# rp3a-mini-power.net
KiCad netlist of a schematic drawn in Altium Designer
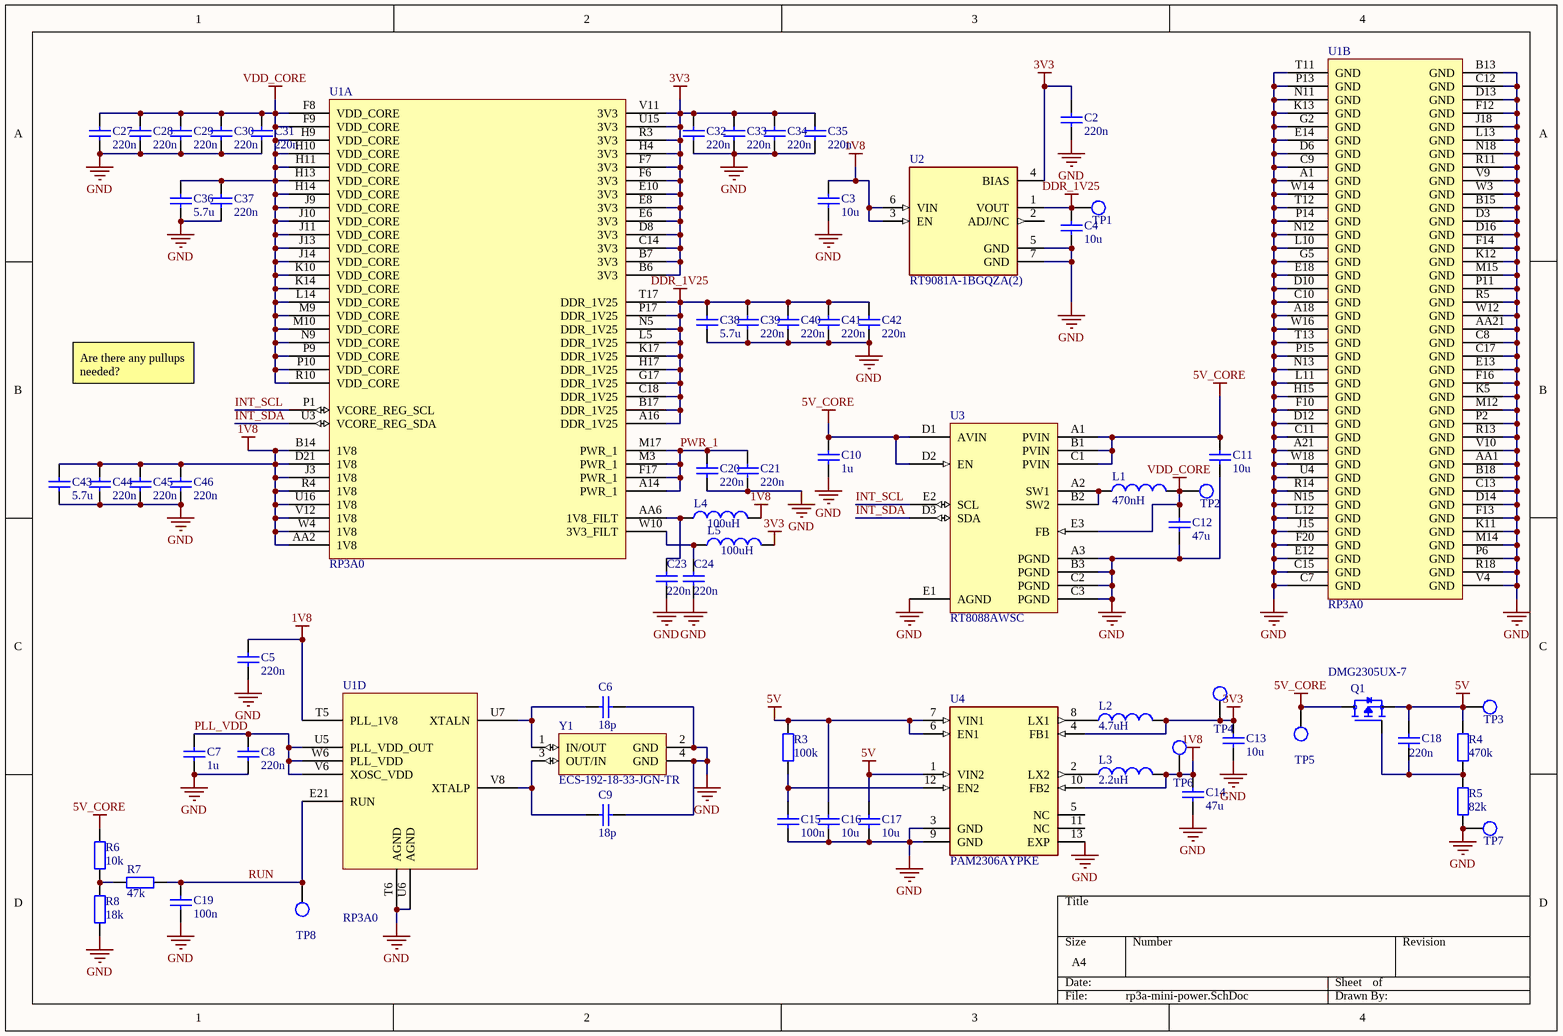
[diagram p0: rp3a-mini-power.SchDoc]

(export (version "E")
  (design (tool "Eeschema 10.0.6"))
  (components
    (comp (ref "C2")
      (value "220n")
      (footprint "0402")
      (description "Capacitor")
      (fields (field (name "Comment") "Cap"))
      (libsource (lib "custom-lib") (part "CAP-NONPOL"))
    )
    (comp (ref "C3")
      (value "10u")
      (footprint "0603")
      (description "Capacitor")
      (fields (field (name "Comment") "Cap"))
      (libsource (lib "custom-lib") (part "CAP-NONPOL"))
    )
    (comp (ref "C4")
      (value "10u")
      (footprint "0603")
      (description "Capacitor")
      (fields (field (name "Comment") "Cap"))
      (libsource (lib "custom-lib") (part "CAP-NONPOL"))
    )
    (comp (ref "C5")
      (value "220n")
      (footprint "0402")
      (description "Capacitor")
      (fields (field (name "Comment") "Cap"))
      (libsource (lib "custom-lib") (part "CAP-NONPOL"))
    )
    (comp (ref "C6")
      (value "18p")
      (footprint "0402")
      (description "Capacitor")
      (fields (field (name "Comment") "Cap"))
      (libsource (lib "custom-lib") (part "CAP-NONPOL"))
    )
    (comp (ref "C7")
      (value "1u")
      (footprint "0402")
      (description "Capacitor")
      (fields (field (name "Comment") "Cap"))
      (libsource (lib "custom-lib") (part "CAP-NONPOL"))
    )
    (comp (ref "C8")
      (value "220n")
      (footprint "0402")
      (description "Capacitor")
      (fields (field (name "Comment") "Cap"))
      (libsource (lib "custom-lib") (part "CAP-NONPOL"))
    )
    (comp (ref "C9")
      (value "18p")
      (footprint "0402")
      (description "Capacitor")
      (fields (field (name "Comment") "Cap"))
      (libsource (lib "custom-lib") (part "CAP-NONPOL"))
    )
    (comp (ref "C10")
      (value "1u")
      (footprint "0402")
      (description "Capacitor")
      (fields (field (name "Comment") "Cap"))
      (libsource (lib "custom-lib") (part "CAP-NONPOL"))
    )
    (comp (ref "C11")
      (value "10u")
      (footprint "0603")
      (description "Capacitor")
      (fields (field (name "Comment") "Cap"))
      (libsource (lib "custom-lib") (part "CAP-NONPOL"))
    )
    (comp (ref "C12")
      (value "47u")
      (footprint "C0805 NP")
      (description "Capacitor")
      (fields (field (name "Comment") "Cap"))
      (libsource (lib "custom-lib") (part "CAP-NONPOL"))
    )
    (comp (ref "C13")
      (value "10u")
      (footprint "0603")
      (description "Capacitor")
      (fields (field (name "Comment") "Cap"))
      (libsource (lib "custom-lib") (part "CAP-NONPOL"))
    )
    (comp (ref "C14")
      (value "47u")
      (footprint "C0805 NP")
      (description "Capacitor")
      (fields (field (name "Comment") "Cap"))
      (libsource (lib "custom-lib") (part "CAP-NONPOL"))
    )
    (comp (ref "C15")
      (value "100n")
      (footprint "0402")
      (description "Capacitor")
      (fields (field (name "Comment") "Cap"))
      (libsource (lib "custom-lib") (part "CAP-NONPOL"))
    )
    (comp (ref "C16")
      (value "10u")
      (footprint "0603")
      (description "Capacitor")
      (fields (field (name "Comment") "Cap"))
      (libsource (lib "custom-lib") (part "CAP-NONPOL"))
    )
    (comp (ref "C17")
      (value "10u")
      (footprint "0603")
      (description "Capacitor")
      (fields (field (name "Comment") "Cap"))
      (libsource (lib "custom-lib") (part "CAP-NONPOL"))
    )
    (comp (ref "C18")
      (value "220n")
      (footprint "0402")
      (description "Capacitor")
      (fields (field (name "Comment") "Cap"))
      (libsource (lib "custom-lib") (part "CAP-NONPOL"))
    )
    (comp (ref "C19")
      (value "100n")
      (footprint "0402")
      (description "Capacitor")
      (fields (field (name "Comment") "Cap"))
      (libsource (lib "custom-lib") (part "CAP-NONPOL"))
    )
    (comp (ref "C20")
      (value "220n")
      (footprint "0402")
      (description "Capacitor")
      (fields (field (name "Comment") "Cap"))
      (libsource (lib "custom-lib") (part "CAP-NONPOL"))
    )
    (comp (ref "C21")
      (value "220n")
      (footprint "0402")
      (description "Capacitor")
      (fields (field (name "Comment") "Cap"))
      (libsource (lib "custom-lib") (part "CAP-NONPOL"))
    )
    (comp (ref "C23")
      (value "220n")
      (footprint "0402")
      (description "Capacitor")
      (fields (field (name "Comment") "Cap"))
      (libsource (lib "custom-lib") (part "CAP-NONPOL"))
    )
    (comp (ref "C24")
      (value "220n")
      (footprint "0402")
      (description "Capacitor")
      (fields (field (name "Comment") "Cap"))
      (libsource (lib "custom-lib") (part "CAP-NONPOL"))
    )
    (comp (ref "C27")
      (value "220n")
      (footprint "0402")
      (description "Capacitor")
      (fields (field (name "Comment") "Cap"))
      (libsource (lib "custom-lib") (part "CAP-NONPOL"))
    )
    (comp (ref "C28")
      (value "220n")
      (footprint "0402")
      (description "Capacitor")
      (fields (field (name "Comment") "Cap"))
      (libsource (lib "custom-lib") (part "CAP-NONPOL"))
    )
    (comp (ref "C29")
      (value "220n")
      (footprint "0402")
      (description "Capacitor")
      (fields (field (name "Comment") "Cap"))
      (libsource (lib "custom-lib") (part "CAP-NONPOL"))
    )
    (comp (ref "C30")
      (value "220n")
      (footprint "0402")
      (description "Capacitor")
      (fields (field (name "Comment") "Cap"))
      (libsource (lib "custom-lib") (part "CAP-NONPOL"))
    )
    (comp (ref "C31")
      (value "220n")
      (footprint "0402")
      (description "Capacitor")
      (fields (field (name "Comment") "Cap"))
      (libsource (lib "custom-lib") (part "CAP-NONPOL"))
    )
    (comp (ref "C32")
      (value "220n")
      (footprint "0402")
      (description "Capacitor")
      (fields (field (name "Comment") "Cap"))
      (libsource (lib "custom-lib") (part "CAP-NONPOL"))
    )
    (comp (ref "C33")
      (value "220n")
      (footprint "0402")
      (description "Capacitor")
      (fields (field (name "Comment") "Cap"))
      (libsource (lib "custom-lib") (part "CAP-NONPOL"))
    )
    (comp (ref "C34")
      (value "220n")
      (footprint "0402")
      (description "Capacitor")
      (fields (field (name "Comment") "Cap"))
      (libsource (lib "custom-lib") (part "CAP-NONPOL"))
    )
    (comp (ref "C35")
      (value "220n")
      (footprint "0402")
      (description "Capacitor")
      (fields (field (name "Comment") "Cap"))
      (libsource (lib "custom-lib") (part "CAP-NONPOL"))
    )
    (comp (ref "C36")
      (value "5.7u")
      (footprint "0603")
      (description "Capacitor")
      (fields (field (name "Comment") "Cap"))
      (libsource (lib "custom-lib") (part "CAP-NONPOL"))
    )
    (comp (ref "C37")
      (value "220n")
      (footprint "0402")
      (description "Capacitor")
      (fields (field (name "Comment") "Cap"))
      (libsource (lib "custom-lib") (part "CAP-NONPOL"))
    )
    (comp (ref "C38")
      (value "5.7u")
      (footprint "0603")
      (description "Capacitor")
      (fields (field (name "Comment") "Cap"))
      (libsource (lib "custom-lib") (part "CAP-NONPOL"))
    )
    (comp (ref "C39")
      (value "220n")
      (footprint "0402")
      (description "Capacitor")
      (fields (field (name "Comment") "Cap"))
      (libsource (lib "custom-lib") (part "CAP-NONPOL"))
    )
    (comp (ref "C40")
      (value "220n")
      (footprint "0402")
      (description "Capacitor")
      (fields (field (name "Comment") "Cap"))
      (libsource (lib "custom-lib") (part "CAP-NONPOL"))
    )
    (comp (ref "C41")
      (value "220n")
      (footprint "0402")
      (description "Capacitor")
      (fields (field (name "Comment") "Cap"))
      (libsource (lib "custom-lib") (part "CAP-NONPOL"))
    )
    (comp (ref "C42")
      (value "220n")
      (footprint "0402")
      (description "Capacitor")
      (fields (field (name "Comment") "Cap"))
      (libsource (lib "custom-lib") (part "CAP-NONPOL"))
    )
    (comp (ref "C43")
      (value "5.7u")
      (footprint "0603")
      (description "Capacitor")
      (fields (field (name "Comment") "Cap"))
      (libsource (lib "custom-lib") (part "CAP-NONPOL"))
    )
    (comp (ref "C44")
      (value "220n")
      (footprint "0402")
      (description "Capacitor")
      (fields (field (name "Comment") "Cap"))
      (libsource (lib "custom-lib") (part "CAP-NONPOL"))
    )
    (comp (ref "C45")
      (value "220n")
      (footprint "0402")
      (description "Capacitor")
      (fields (field (name "Comment") "Cap"))
      (libsource (lib "custom-lib") (part "CAP-NONPOL"))
    )
    (comp (ref "C46")
      (value "220n")
      (footprint "0402")
      (description "Capacitor")
      (fields (field (name "Comment") "Cap"))
      (libsource (lib "custom-lib") (part "CAP-NONPOL"))
    )
    (comp (ref "L1")
      (value "470nH")
      (footprint "INDC2016X100N")
      (description "Inductor SMD")
      (fields (field (name "Comment") "INDUCTOR"))
      (libsource (lib "passives") (part "INDUCTOR"))
    )
    (comp (ref "L2")
      (value "4.7uH")
      (footprint "INDP4040X180N")
      (description "Inductor SMD")
      (fields (field (name "Comment") "INDUCTOR"))
      (libsource (lib "custom-lib") (part "INDUCTOR"))
    )
    (comp (ref "L3")
      (value "2.2uH")
      (footprint "INDP2622X120N")
      (description "Inductor SMD")
      (fields (field (name "Comment") "INDUCTOR"))
      (libsource (lib "custom-lib") (part "INDUCTOR"))
    )
    (comp (ref "L4")
      (value "100uH")
      (footprint "0402")
      (description "Inductor SMD")
      (fields (field (name "Comment") "INDUCTOR"))
      (libsource (lib "custom-lib") (part "INDUCTOR"))
    )
    (comp (ref "L5")
      (value "100uH")
      (footprint "0402")
      (description "Inductor SMD")
      (fields (field (name "Comment") "INDUCTOR"))
      (libsource (lib "custom-lib") (part "INDUCTOR"))
    )
    (comp (ref "Q1")
      (value "DMG2305UX-7")
      (footprint "SOT91P240X110-3N_DMG2305UX-7")
      (description "P-Channel 20V 4.2A _Ta_ 1.4W _Ta_ Surface Mount SOT-23")
      (fields (field (name "MF") "Power Analog Micro"))
      (libsource (lib "custom-lib") (part "DMG2305UX-7"))
    )
    (comp (ref "R3")
      (value "100k")
      (footprint "RES-0402-SML")
      (description "Resistor")
      (fields (field (name "Comment") "Res SMD"))
      (libsource (lib "custom-lib") (part "Res SMD"))
    )
    (comp (ref "R4")
      (value "470k")
      (footprint "RES-0402-SML")
      (description "Resistor")
      (fields (field (name "Comment") "Res SMD"))
      (libsource (lib "custom-lib") (part "Res SMD"))
    )
    (comp (ref "R5")
      (value "82k")
      (footprint "RES-0402-SML")
      (description "Resistor")
      (fields (field (name "Comment") "Res SMD"))
      (libsource (lib "") (part "Res SMD_1"))
    )
    (comp (ref "R6")
      (value "10k")
      (footprint "RES-0402-SML")
      (description "Resistor")
      (fields (field (name "Comment") "Res SMD"))
      (libsource (lib "custom-lib") (part "Res SMD"))
    )
    (comp (ref "R7")
      (value "47k")
      (footprint "RES-0402-SML")
      (description "Resistor")
      (fields (field (name "Comment") "Res SMD"))
      (libsource (lib "") (part "Res SMD_2"))
    )
    (comp (ref "R8")
      (value "18k")
      (footprint "RES-0402-SML")
      (description "Resistor")
      (fields (field (name "Comment") "Res SMD"))
      (libsource (lib "custom-lib") (part "Res SMD"))
    )
    (comp (ref "TP1")
      (value "TEST_POINT")
      (footprint "TEST_POINT_1.2MM")
      (description "Test point")
      (libsource (lib "custom-lib") (part "TEST_POINT"))
    )
    (comp (ref "TP2")
      (value "TEST_POINT")
      (footprint "TEST_POINT_1.2MM")
      (description "Test point")
      (libsource (lib "custom-lib") (part "TEST_POINT"))
    )
    (comp (ref "TP3")
      (value "TEST_POINT")
      (footprint "TEST_POINT_1.2MM")
      (description "Test point")
      (libsource (lib "custom-lib") (part "TEST_POINT"))
    )
    (comp (ref "TP4")
      (value "TEST_POINT")
      (footprint "TEST_POINT_1.2MM")
      (description "Test point")
      (libsource (lib "custom-lib") (part "TEST_POINT"))
    )
    (comp (ref "TP5")
      (value "TEST_POINT")
      (footprint "TEST_POINT_1.2MM")
      (description "Test point")
      (libsource (lib "custom-lib") (part "TEST_POINT"))
    )
    (comp (ref "TP6")
      (value "TEST_POINT")
      (footprint "TEST_POINT_1.2MM")
      (description "Test point")
      (libsource (lib "custom-lib") (part "TEST_POINT"))
    )
    (comp (ref "TP7")
      (value "TEST_POINT")
      (footprint "TEST_POINT_1.2MM")
      (description "Test point")
      (libsource (lib "custom-lib") (part "TEST_POINT"))
    )
    (comp (ref "TP8")
      (value "TEST_POINT")
      (footprint "TEST_POINT_1.2MM")
      (description "Test point")
      (libsource (lib "custom-lib") (part "TEST_POINT"))
    )
    (comp (ref "U1") (value "RP3A0") (footprint "RP3A0-BGA") (libsource (lib "rp3a0") (part "RP3A0")))
    (comp (ref "U2")
      (value "RT9081A-1BGQZA(2)")
      (footprint "VREG_RT9081A_1BGQZA(2)")
      (description "Linear Voltage Regulator IC 1 Output 500mA 6-ZADFN (1.2x1.2)")
      (fields (field (name "MP") "RT9081AGQZA") (field (name "MF") "Richtek USA"))
      (libsource (lib "richtek") (part "RT9081A-1BGQZA(2)"))
    )
    (comp (ref "U3")
      (value "RT8088AWSC")
      (footprint "15B_WLCSP_1.31x2.11")
      (description "Buck Switching Regulator IC Positive Programmable 0.6V 1 Output 3A 15-UFBGA, WLCSP")
      (libsource (lib "richtek") (part "RT8088AWSC"))
    )
    (comp (ref "U4")
      (value "PAM2306AYPKE")
      (footprint "SON45P300X300X80-13N")
      (description "Buck Switching Regulator IC Positive Fixed 1.8V, 3.3V 2 Output 1A 12-WFDFN Exposed Pad")
      (fields (field (name "MF") "Diodes Inc."))
      (libsource (lib "custom-lib") (part "PAM2306AYPKE"))
    )
    (comp (ref "Y1")
      (value "ECS-192-18-33-JGN-TR")
      (footprint "XTAL_ECS-192-18-33-JGN-TR")
      (libsource (lib "custom-lib") (part "ECS-192-18-33-JGN-TR"))
    )
  )
  (nets
    (net (code "1") (name "/INT_SCL") (class "Default")
      (node (ref "U1") (pin "P1") (pinfunction "VCORE_REG_SCL_P1") (pintype "bidirectional"))
      (node (ref "U3") (pin "E2") (pinfunction "SCL_E2") (pintype "bidirectional"))
    )
    (net (code "2") (name "/INT_SDA") (class "Default")
      (node (ref "U1") (pin "U3") (pinfunction "VCORE_REG_SDA_U3") (pintype "bidirectional"))
      (node (ref "U3") (pin "D3") (pinfunction "SDA_D3") (pintype "bidirectional"))
    )
    (net (code "3") (name "/PLL_VDD") (class "Default")
      (node (ref "C7") (pin "2") (pinfunction "2_2") (pintype "passive"))
      (node (ref "C8") (pin "2") (pinfunction "2_2") (pintype "passive"))
      (node (ref "U1") (pin "U5") (pinfunction "PLL_VDD_OUT_U5") (pintype "passive"))
      (node (ref "U1") (pin "V6") (pinfunction "XOSC_VDD_V6") (pintype "passive"))
      (node (ref "U1") (pin "W6") (pinfunction "PLL_VDD_W6") (pintype "passive"))
    )
    (net (code "4") (name "/PWR_1") (class "Default")
      (node (ref "C20") (pin "2") (pinfunction "2_2") (pintype "passive"))
      (node (ref "C21") (pin "2") (pinfunction "2_2") (pintype "passive"))
      (node (ref "U1") (pin "A14") (pinfunction "PWR_1_A14") (pintype "power_in"))
      (node (ref "U1") (pin "F17") (pinfunction "PWR_1_F17") (pintype "power_in"))
      (node (ref "U1") (pin "M17") (pinfunction "PWR_1_M17") (pintype "power_in"))
      (node (ref "U1") (pin "M3") (pinfunction "PWR_1_M3") (pintype "power_in"))
    )
    (net (code "5") (name "/RUN") (class "Default")
      (node (ref "C19") (pin "2") (pinfunction "2_2") (pintype "passive"))
      (node (ref "R7") (pin "2") (pinfunction "2_2") (pintype "passive"))
      (node (ref "TP8") (pin "TP") (pintype "passive"))
      (node (ref "U1") (pin "E21") (pinfunction "RUN_E21") (pintype "passive"))
    )
    (net (code "6") (name "1V8") (class "Default")
      (node (ref "C14") (pin "2") (pinfunction "2_2") (pintype "passive"))
      (node (ref "C3") (pin "2") (pinfunction "2_2") (pintype "passive"))
      (node (ref "C43") (pin "2") (pinfunction "2_2") (pintype "passive"))
      (node (ref "C44") (pin "2") (pinfunction "2_2") (pintype "passive"))
      (node (ref "C45") (pin "2") (pinfunction "2_2") (pintype "passive"))
      (node (ref "C46") (pin "2") (pinfunction "2_2") (pintype "passive"))
      (node (ref "C5") (pin "2") (pinfunction "2_2") (pintype "passive"))
      (node (ref "L3") (pin "2") (pinfunction "2_2") (pintype "passive"))
      (node (ref "L4") (pin "2") (pinfunction "2_2") (pintype "passive"))
      (node (ref "TP6") (pin "TP") (pintype "passive"))
      (node (ref "U1") (pin "AA2") (pinfunction "1V8_AA2") (pintype "power_in"))
      (node (ref "U1") (pin "B14") (pinfunction "1V8_B14") (pintype "power_in"))
      (node (ref "U1") (pin "D21") (pinfunction "1V8_D21") (pintype "power_in"))
      (node (ref "U1") (pin "J3") (pinfunction "1V8_J3") (pintype "power_in"))
      (node (ref "U1") (pin "R4") (pinfunction "1V8_R4") (pintype "power_in"))
      (node (ref "U1") (pin "T5") (pinfunction "PLL_1V8_T5") (pintype "passive"))
      (node (ref "U1") (pin "U16") (pinfunction "1V8_U16") (pintype "power_in"))
      (node (ref "U1") (pin "V12") (pinfunction "1V8_V12") (pintype "power_in"))
      (node (ref "U1") (pin "W4") (pinfunction "1V8_W4") (pintype "power_in"))
      (node (ref "U2") (pin "3") (pinfunction "EN_3") (pintype "input"))
      (node (ref "U2") (pin "6") (pinfunction "VIN_6") (pintype "input"))
      (node (ref "U4") (pin "10") (pinfunction "FB2_10") (pintype "input"))
    )
    (net (code "7") (name "3V3") (class "Default")
      (node (ref "C13") (pin "2") (pinfunction "2_2") (pintype "passive"))
      (node (ref "C2") (pin "2") (pinfunction "2_2") (pintype "passive"))
      (node (ref "C32") (pin "2") (pinfunction "2_2") (pintype "passive"))
      (node (ref "C33") (pin "2") (pinfunction "2_2") (pintype "passive"))
      (node (ref "C34") (pin "2") (pinfunction "2_2") (pintype "passive"))
      (node (ref "C35") (pin "2") (pinfunction "2_2") (pintype "passive"))
      (node (ref "L2") (pin "2") (pinfunction "2_2") (pintype "passive"))
      (node (ref "L5") (pin "2") (pinfunction "2_2") (pintype "passive"))
      (node (ref "TP4") (pin "TP") (pintype "passive"))
      (node (ref "U1") (pin "B6") (pinfunction "3V3_B6") (pintype "power_in"))
      (node (ref "U1") (pin "B7") (pinfunction "3V3_B7") (pintype "power_in"))
      (node (ref "U1") (pin "C14") (pinfunction "3V3_C14") (pintype "power_in"))
      (node (ref "U1") (pin "D8") (pinfunction "3V3_D8") (pintype "power_in"))
      (node (ref "U1") (pin "E10") (pinfunction "3V3_E10") (pintype "power_in"))
      (node (ref "U1") (pin "E6") (pinfunction "3V3_E6") (pintype "power_in"))
      (node (ref "U1") (pin "E8") (pinfunction "3V3_E8") (pintype "power_in"))
      (node (ref "U1") (pin "F6") (pinfunction "3V3_F6") (pintype "power_in"))
      (node (ref "U1") (pin "F7") (pinfunction "3V3_F7") (pintype "power_in"))
      (node (ref "U1") (pin "H4") (pinfunction "3V3_H4") (pintype "power_in"))
      (node (ref "U1") (pin "R3") (pinfunction "3V3_R3") (pintype "power_in"))
      (node (ref "U1") (pin "U15") (pinfunction "3V3_U15") (pintype "power_in"))
      (node (ref "U1") (pin "V11") (pinfunction "3V3_V11") (pintype "power_in"))
      (node (ref "U2") (pin "4") (pinfunction "BIAS_4") (pintype "power_in"))
      (node (ref "U4") (pin "4") (pinfunction "FB1_4") (pintype "input"))
    )
    (net (code "8") (name "5V") (class "Default")
      (node (ref "C16") (pin "2") (pinfunction "2_2") (pintype "passive"))
      (node (ref "C17") (pin "2") (pinfunction "2_2") (pintype "passive"))
      (node (ref "C18") (pin "2") (pinfunction "2_2") (pintype "passive"))
      (node (ref "Q1") (pin "2") (pinfunction "S_2") (pintype "passive"))
      (node (ref "R3") (pin "2") (pinfunction "2_2") (pintype "passive"))
      (node (ref "R4") (pin "2") (pinfunction "2_2") (pintype "passive"))
      (node (ref "TP3") (pin "TP") (pintype "passive"))
      (node (ref "U4") (pin "1") (pinfunction "VIN2_1") (pintype "input"))
      (node (ref "U4") (pin "6") (pinfunction "EN1_6") (pintype "input"))
      (node (ref "U4") (pin "7") (pinfunction "VIN1_7") (pintype "input"))
    )
    (net (code "9") (name "5V_CORE") (class "Default")
      (node (ref "C10") (pin "2") (pinfunction "2_2") (pintype "passive"))
      (node (ref "C11") (pin "2") (pinfunction "2_2") (pintype "passive"))
      (node (ref "Q1") (pin "3") (pinfunction "D_3") (pintype "passive"))
      (node (ref "R6") (pin "2") (pinfunction "2_2") (pintype "passive"))
      (node (ref "TP5") (pin "TP") (pintype "passive"))
      (node (ref "U3") (pin "A1") (pinfunction "PVIN_A1") (pintype "power_in"))
      (node (ref "U3") (pin "B1") (pinfunction "PVIN_B1") (pintype "power_in"))
      (node (ref "U3") (pin "C1") (pinfunction "PVIN_C1") (pintype "power_in"))
      (node (ref "U3") (pin "D1") (pinfunction "AVIN_D1") (pintype "power_in"))
      (node (ref "U3") (pin "D2") (pinfunction "EN_D2") (pintype "input"))
    )
    (net (code "10") (name "DDR_1V25") (class "Default")
      (node (ref "C38") (pin "2") (pinfunction "2_2") (pintype "passive"))
      (node (ref "C39") (pin "2") (pinfunction "2_2") (pintype "passive"))
      (node (ref "C4") (pin "2") (pinfunction "2_2") (pintype "passive"))
      (node (ref "C40") (pin "2") (pinfunction "2_2") (pintype "passive"))
      (node (ref "C41") (pin "2") (pinfunction "2_2") (pintype "passive"))
      (node (ref "C42") (pin "2") (pinfunction "2_2") (pintype "passive"))
      (node (ref "TP1") (pin "TP") (pintype "passive"))
      (node (ref "U1") (pin "A16") (pinfunction "DDR_1V25_A16") (pintype "power_in"))
      (node (ref "U1") (pin "B17") (pinfunction "DDR_1V25_B17") (pintype "power_in"))
      (node (ref "U1") (pin "C18") (pinfunction "DDR_1V25_C18") (pintype "power_in"))
      (node (ref "U1") (pin "G17") (pinfunction "DDR_1V25_G17") (pintype "power_in"))
      (node (ref "U1") (pin "H17") (pinfunction "DDR_1V25_H17") (pintype "power_in"))
      (node (ref "U1") (pin "K17") (pinfunction "DDR_1V25_K17") (pintype "power_in"))
      (node (ref "U1") (pin "L5") (pinfunction "DDR_1V25_L5") (pintype "power_in"))
      (node (ref "U1") (pin "N5") (pinfunction "DDR_1V25_N5") (pintype "power_in"))
      (node (ref "U1") (pin "P17") (pinfunction "DDR_1V25_P17") (pintype "power_in"))
      (node (ref "U1") (pin "T17") (pinfunction "DDR_1V25_T17") (pintype "power_in"))
      (node (ref "U2") (pin "1") (pinfunction "VOUT_1") (pintype "power_in"))
    )
    (net (code "11") (name "GND") (class "Default")
      (node (ref "C10") (pin "1") (pinfunction "1_1") (pintype "passive"))
      (node (ref "C11") (pin "1") (pinfunction "1_1") (pintype "passive"))
      (node (ref "C12") (pin "1") (pinfunction "1_1") (pintype "passive"))
      (node (ref "C13") (pin "1") (pinfunction "1_1") (pintype "passive"))
      (node (ref "C14") (pin "1") (pinfunction "1_1") (pintype "passive"))
      (node (ref "C15") (pin "1") (pinfunction "1_1") (pintype "passive"))
      (node (ref "C16") (pin "1") (pinfunction "1_1") (pintype "passive"))
      (node (ref "C17") (pin "1") (pinfunction "1_1") (pintype "passive"))
      (node (ref "C19") (pin "1") (pinfunction "1_1") (pintype "passive"))
      (node (ref "C2") (pin "1") (pinfunction "1_1") (pintype "passive"))
      (node (ref "C20") (pin "1") (pinfunction "1_1") (pintype "passive"))
      (node (ref "C21") (pin "1") (pinfunction "1_1") (pintype "passive"))
      (node (ref "C23") (pin "1") (pinfunction "1_1") (pintype "passive"))
      (node (ref "C24") (pin "1") (pinfunction "1_1") (pintype "passive"))
      (node (ref "C27") (pin "1") (pinfunction "1_1") (pintype "passive"))
      (node (ref "C28") (pin "1") (pinfunction "1_1") (pintype "passive"))
      (node (ref "C29") (pin "1") (pinfunction "1_1") (pintype "passive"))
      (node (ref "C3") (pin "1") (pinfunction "1_1") (pintype "passive"))
      (node (ref "C30") (pin "1") (pinfunction "1_1") (pintype "passive"))
      (node (ref "C31") (pin "1") (pinfunction "1_1") (pintype "passive"))
      (node (ref "C32") (pin "1") (pinfunction "1_1") (pintype "passive"))
      (node (ref "C33") (pin "1") (pinfunction "1_1") (pintype "passive"))
      (node (ref "C34") (pin "1") (pinfunction "1_1") (pintype "passive"))
      (node (ref "C35") (pin "1") (pinfunction "1_1") (pintype "passive"))
      (node (ref "C36") (pin "1") (pinfunction "1_1") (pintype "passive"))
      (node (ref "C37") (pin "1") (pinfunction "1_1") (pintype "passive"))
      (node (ref "C38") (pin "1") (pinfunction "1_1") (pintype "passive"))
      (node (ref "C39") (pin "1") (pinfunction "1_1") (pintype "passive"))
      (node (ref "C4") (pin "1") (pinfunction "1_1") (pintype "passive"))
      (node (ref "C40") (pin "1") (pinfunction "1_1") (pintype "passive"))
      (node (ref "C41") (pin "1") (pinfunction "1_1") (pintype "passive"))
      (node (ref "C42") (pin "1") (pinfunction "1_1") (pintype "passive"))
      (node (ref "C43") (pin "1") (pinfunction "1_1") (pintype "passive"))
      (node (ref "C44") (pin "1") (pinfunction "1_1") (pintype "passive"))
      (node (ref "C45") (pin "1") (pinfunction "1_1") (pintype "passive"))
      (node (ref "C46") (pin "1") (pinfunction "1_1") (pintype "passive"))
      (node (ref "C5") (pin "1") (pinfunction "1_1") (pintype "passive"))
      (node (ref "C6") (pin "2") (pinfunction "2_2") (pintype "passive"))
      (node (ref "C7") (pin "1") (pinfunction "1_1") (pintype "passive"))
      (node (ref "C8") (pin "1") (pinfunction "1_1") (pintype "passive"))
      (node (ref "C9") (pin "2") (pinfunction "2_2") (pintype "passive"))
      (node (ref "R5") (pin "2") (pinfunction "2_2") (pintype "passive"))
      (node (ref "R8") (pin "1") (pinfunction "1_1") (pintype "passive"))
      (node (ref "TP7") (pin "TP") (pintype "passive"))
      (node (ref "U1") (pin "A1") (pinfunction "GND_A1") (pintype "passive"))
      (node (ref "U1") (pin "A18") (pinfunction "GND_A18") (pintype "passive"))
      (node (ref "U1") (pin "A21") (pinfunction "GND_A21") (pintype "passive"))
      (node (ref "U1") (pin "AA1") (pinfunction "GND_AA1") (pintype "passive"))
      (node (ref "U1") (pin "AA21") (pinfunction "GND_AA21") (pintype "passive"))
      (node (ref "U1") (pin "B13") (pinfunction "GND_B13") (pintype "passive"))
      (node (ref "U1") (pin "B15") (pinfunction "GND_B15") (pintype "passive"))
      (node (ref "U1") (pin "B18") (pinfunction "GND_B18") (pintype "passive"))
      (node (ref "U1") (pin "C10") (pinfunction "GND_C10") (pintype "passive"))
      (node (ref "U1") (pin "C11") (pinfunction "GND_C11") (pintype "passive"))
      (node (ref "U1") (pin "C12") (pinfunction "GND_C12") (pintype "passive"))
      (node (ref "U1") (pin "C13") (pinfunction "GND_C13") (pintype "passive"))
      (node (ref "U1") (pin "C15") (pinfunction "GND_C15") (pintype "passive"))
      (node (ref "U1") (pin "C17") (pinfunction "GND_C17") (pintype "passive"))
      (node (ref "U1") (pin "C7") (pinfunction "GND_C7") (pintype "passive"))
      (node (ref "U1") (pin "C8") (pinfunction "GND_C8") (pintype "passive"))
      (node (ref "U1") (pin "C9") (pinfunction "GND_C9") (pintype "passive"))
      (node (ref "U1") (pin "D10") (pinfunction "GND_D10") (pintype "passive"))
      (node (ref "U1") (pin "D12") (pinfunction "GND_D12") (pintype "passive"))
      (node (ref "U1") (pin "D13") (pinfunction "GND_D13") (pintype "passive"))
      (node (ref "U1") (pin "D14") (pinfunction "GND_D14") (pintype "passive"))
      (node (ref "U1") (pin "D16") (pinfunction "GND_D16") (pintype "passive"))
      (node (ref "U1") (pin "D3") (pinfunction "GND_D3") (pintype "passive"))
      (node (ref "U1") (pin "D6") (pinfunction "GND_D6") (pintype "passive"))
      (node (ref "U1") (pin "E12") (pinfunction "GND_E12") (pintype "passive"))
      (node (ref "U1") (pin "E13") (pinfunction "GND_E13") (pintype "passive"))
      (node (ref "U1") (pin "E14") (pinfunction "GND_E14") (pintype "passive"))
      (node (ref "U1") (pin "E18") (pinfunction "GND_E18") (pintype "passive"))
      (node (ref "U1") (pin "F10") (pinfunction "GND_F10") (pintype "passive"))
      (node (ref "U1") (pin "F12") (pinfunction "GND_F12") (pintype "passive"))
      (node (ref "U1") (pin "F13") (pinfunction "GND_F13") (pintype "passive"))
      (node (ref "U1") (pin "F14") (pinfunction "GND_F14") (pintype "passive"))
      (node (ref "U1") (pin "F16") (pinfunction "GND_F16") (pintype "passive"))
      (node (ref "U1") (pin "F20") (pinfunction "GND_F20") (pintype "passive"))
      (node (ref "U1") (pin "G2") (pinfunction "GND_G2") (pintype "passive"))
      (node (ref "U1") (pin "G5") (pinfunction "GND_G5") (pintype "passive"))
      (node (ref "U1") (pin "H15") (pinfunction "GND_H15") (pintype "passive"))
      (node (ref "U1") (pin "J15") (pinfunction "GND_J15") (pintype "passive"))
      (node (ref "U1") (pin "J18") (pinfunction "GND_J18") (pintype "passive"))
      (node (ref "U1") (pin "K11") (pinfunction "GND_K11") (pintype "passive"))
      (node (ref "U1") (pin "K12") (pinfunction "GND_K12") (pintype "passive"))
      (node (ref "U1") (pin "K13") (pinfunction "GND_K13") (pintype "passive"))
      (node (ref "U1") (pin "K5") (pinfunction "GND_K5") (pintype "passive"))
      (node (ref "U1") (pin "L10") (pinfunction "GND_L10") (pintype "passive"))
      (node (ref "U1") (pin "L11") (pinfunction "GND_L11") (pintype "passive"))
      (node (ref "U1") (pin "L12") (pinfunction "GND_L12") (pintype "passive"))
      (node (ref "U1") (pin "L13") (pinfunction "GND_L13") (pintype "passive"))
      (node (ref "U1") (pin "M12") (pinfunction "GND_M12") (pintype "passive"))
      (node (ref "U1") (pin "M14") (pinfunction "GND_M14") (pintype "passive"))
      (node (ref "U1") (pin "M15") (pinfunction "GND_M15") (pintype "passive"))
      (node (ref "U1") (pin "N11") (pinfunction "GND_N11") (pintype "passive"))
      (node (ref "U1") (pin "N12") (pinfunction "GND_N12") (pintype "passive"))
      (node (ref "U1") (pin "N13") (pinfunction "GND_N13") (pintype "passive"))
      (node (ref "U1") (pin "N15") (pinfunction "GND_N15") (pintype "passive"))
      (node (ref "U1") (pin "N18") (pinfunction "GND_N18") (pintype "passive"))
      (node (ref "U1") (pin "P11") (pinfunction "GND_P11") (pintype "passive"))
      (node (ref "U1") (pin "P13") (pinfunction "GND_P13") (pintype "passive"))
      (node (ref "U1") (pin "P14") (pinfunction "GND_P14") (pintype "passive"))
      (node (ref "U1") (pin "P15") (pinfunction "GND_P15") (pintype "passive"))
      (node (ref "U1") (pin "P2") (pinfunction "GND_P2") (pintype "passive"))
      (node (ref "U1") (pin "P6") (pinfunction "GND_P6") (pintype "passive"))
      (node (ref "U1") (pin "R11") (pinfunction "GND_R11") (pintype "passive"))
      (node (ref "U1") (pin "R13") (pinfunction "GND_R13") (pintype "passive"))
      (node (ref "U1") (pin "R14") (pinfunction "GND_R14") (pintype "passive"))
      (node (ref "U1") (pin "R18") (pinfunction "GND_R18") (pintype "passive"))
      (node (ref "U1") (pin "R5") (pinfunction "GND_R5") (pintype "passive"))
      (node (ref "U1") (pin "T11") (pinfunction "GND_T11") (pintype "passive"))
      (node (ref "U1") (pin "T12") (pinfunction "GND_T12") (pintype "passive"))
      (node (ref "U1") (pin "T13") (pinfunction "GND_T13") (pintype "passive"))
      (node (ref "U1") (pin "T6") (pinfunction "AGND_T6") (pintype "passive"))
      (node (ref "U1") (pin "U4") (pinfunction "GND_U4") (pintype "passive"))
      (node (ref "U1") (pin "U6") (pinfunction "AGND_U6") (pintype "passive"))
      (node (ref "U1") (pin "V10") (pinfunction "GND_V10") (pintype "passive"))
      (node (ref "U1") (pin "V4") (pinfunction "GND_V4") (pintype "passive"))
      (node (ref "U1") (pin "V9") (pinfunction "GND_V9") (pintype "passive"))
      (node (ref "U1") (pin "W12") (pinfunction "GND_W12") (pintype "passive"))
      (node (ref "U1") (pin "W14") (pinfunction "GND_W14") (pintype "passive"))
      (node (ref "U1") (pin "W16") (pinfunction "GND_W16") (pintype "passive"))
      (node (ref "U1") (pin "W18") (pinfunction "GND_W18") (pintype "passive"))
      (node (ref "U1") (pin "W3") (pinfunction "GND_W3") (pintype "passive"))
      (node (ref "U2") (pin "5") (pinfunction "GND_5") (pintype "power_in"))
      (node (ref "U2") (pin "7") (pinfunction "GND_7") (pintype "power_in"))
      (node (ref "U3") (pin "A3") (pinfunction "PGND_A3") (pintype "passive"))
      (node (ref "U3") (pin "B3") (pinfunction "PGND_B3") (pintype "passive"))
      (node (ref "U3") (pin "C2") (pinfunction "PGND_C2") (pintype "passive"))
      (node (ref "U3") (pin "C3") (pinfunction "PGND_C3") (pintype "passive"))
      (node (ref "U3") (pin "E1") (pinfunction "AGND_E1") (pintype "passive"))
      (node (ref "U4") (pin "13") (pinfunction "EXP_13") (pintype "power_in"))
      (node (ref "U4") (pin "3") (pinfunction "GND_3") (pintype "power_in"))
      (node (ref "U4") (pin "9") (pinfunction "GND_9") (pintype "power_in"))
      (node (ref "Y1") (pin "2") (pinfunction "GND_2") (pintype "power_in"))
      (node (ref "Y1") (pin "4") (pinfunction "GND_4") (pintype "power_in"))
    )
    (net (code "12") (name "Net-(Q1-G)") (class "Default")
      (node (ref "C18") (pin "1") (pinfunction "1_1") (pintype "passive"))
      (node (ref "Q1") (pin "1") (pinfunction "G_1") (pintype "passive"))
      (node (ref "R4") (pin "1") (pinfunction "1_1") (pintype "passive"))
      (node (ref "R5") (pin "1") (pinfunction "1_1") (pintype "passive"))
    )
    (net (code "13") (name "Net-(R6-Pad1)") (class "Default")
      (node (ref "R6") (pin "1") (pinfunction "1_1") (pintype "passive"))
      (node (ref "R7") (pin "1") (pinfunction "1_1") (pintype "passive"))
      (node (ref "R8") (pin "2") (pinfunction "2_2") (pintype "passive"))
    )
    (net (code "14") (name "Net-(U1A-1V8_FILT)") (class "Default")
      (node (ref "C23") (pin "2") (pinfunction "2_2") (pintype "passive"))
      (node (ref "L4") (pin "1") (pinfunction "1_1") (pintype "passive"))
      (node (ref "U1") (pin "AA6") (pinfunction "1V8_FILT_AA6") (pintype "power_in"))
    )
    (net (code "15") (name "Net-(U1A-3V3_FILT)") (class "Default")
      (node (ref "C24") (pin "2") (pinfunction "2_2") (pintype "passive"))
      (node (ref "L5") (pin "1") (pinfunction "1_1") (pintype "passive"))
      (node (ref "U1") (pin "W10") (pinfunction "3V3_FILT_W10") (pintype "power_in"))
    )
    (net (code "16") (name "Net-(U1D-XTALN)") (class "Default")
      (node (ref "C6") (pin "1") (pinfunction "1_1") (pintype "passive"))
      (node (ref "U1") (pin "U7") (pinfunction "XTALN_U7") (pintype "passive"))
      (node (ref "Y1") (pin "1") (pinfunction "IN/OUT_1") (pintype "bidirectional"))
    )
    (net (code "17") (name "Net-(U1D-XTALP)") (class "Default")
      (node (ref "C9") (pin "1") (pinfunction "1_1") (pintype "passive"))
      (node (ref "U1") (pin "V8") (pinfunction "XTALP_V8") (pintype "passive"))
      (node (ref "Y1") (pin "3") (pinfunction "OUT/IN_3") (pintype "bidirectional"))
    )
    (net (code "18") (name "Net-(U3-SW1)") (class "Default")
      (node (ref "L1") (pin "1") (pinfunction "1_1") (pintype "passive"))
      (node (ref "U3") (pin "A2") (pinfunction "SW1_A2") (pintype "passive"))
      (node (ref "U3") (pin "B2") (pinfunction "SW2_B2") (pintype "passive"))
    )
    (net (code "19") (name "Net-(U4-EN2)") (class "Default")
      (node (ref "C15") (pin "2") (pinfunction "2_2") (pintype "passive"))
      (node (ref "R3") (pin "1") (pinfunction "1_1") (pintype "passive"))
      (node (ref "U4") (pin "12") (pinfunction "EN2_12") (pintype "input"))
    )
    (net (code "20") (name "Net-(U4-LX1)") (class "Default")
      (node (ref "L2") (pin "1") (pinfunction "1_1") (pintype "passive"))
      (node (ref "U4") (pin "8") (pinfunction "LX1_8") (pintype "output"))
    )
    (net (code "21") (name "Net-(U4-LX2)") (class "Default")
      (node (ref "L3") (pin "1") (pinfunction "1_1") (pintype "passive"))
      (node (ref "U4") (pin "2") (pinfunction "LX2_2") (pintype "output"))
    )
    (net (code "22") (name "VDD_CORE") (class "Default")
      (node (ref "C12") (pin "2") (pinfunction "2_2") (pintype "passive"))
      (node (ref "C27") (pin "2") (pinfunction "2_2") (pintype "passive"))
      (node (ref "C28") (pin "2") (pinfunction "2_2") (pintype "passive"))
      (node (ref "C29") (pin "2") (pinfunction "2_2") (pintype "passive"))
      (node (ref "C30") (pin "2") (pinfunction "2_2") (pintype "passive"))
      (node (ref "C31") (pin "2") (pinfunction "2_2") (pintype "passive"))
      (node (ref "C36") (pin "2") (pinfunction "2_2") (pintype "passive"))
      (node (ref "C37") (pin "2") (pinfunction "2_2") (pintype "passive"))
      (node (ref "L1") (pin "2") (pinfunction "2_2") (pintype "passive"))
      (node (ref "TP2") (pin "TP") (pintype "passive"))
      (node (ref "U1") (pin "F8") (pinfunction "VDD_CORE_F8") (pintype "power_in"))
      (node (ref "U1") (pin "F9") (pinfunction "VDD_CORE_F9") (pintype "power_in"))
      (node (ref "U1") (pin "H10") (pinfunction "VDD_CORE_H10") (pintype "power_in"))
      (node (ref "U1") (pin "H11") (pinfunction "VDD_CORE_H11") (pintype "power_in"))
      (node (ref "U1") (pin "H13") (pinfunction "VDD_CORE_H13") (pintype "power_in"))
      (node (ref "U1") (pin "H14") (pinfunction "VDD_CORE_H14") (pintype "power_in"))
      (node (ref "U1") (pin "H9") (pinfunction "VDD_CORE_H9") (pintype "power_in"))
      (node (ref "U1") (pin "J10") (pinfunction "VDD_CORE_J10") (pintype "power_in"))
      (node (ref "U1") (pin "J11") (pinfunction "VDD_CORE_J11") (pintype "power_in"))
      (node (ref "U1") (pin "J13") (pinfunction "VDD_CORE_J13") (pintype "power_in"))
      (node (ref "U1") (pin "J14") (pinfunction "VDD_CORE_J14") (pintype "power_in"))
      (node (ref "U1") (pin "J9") (pinfunction "VDD_CORE_J9") (pintype "power_in"))
      (node (ref "U1") (pin "K10") (pinfunction "VDD_CORE_K10") (pintype "power_in"))
      (node (ref "U1") (pin "K14") (pinfunction "VDD_CORE_K14") (pintype "power_in"))
      (node (ref "U1") (pin "L14") (pinfunction "VDD_CORE_L14") (pintype "power_in"))
      (node (ref "U1") (pin "M10") (pinfunction "VDD_CORE_M10") (pintype "power_in"))
      (node (ref "U1") (pin "M9") (pinfunction "VDD_CORE_M9") (pintype "power_in"))
      (node (ref "U1") (pin "N9") (pinfunction "VDD_CORE_N9") (pintype "power_in"))
      (node (ref "U1") (pin "P10") (pinfunction "VDD_CORE_P10") (pintype "power_in"))
      (node (ref "U1") (pin "P9") (pinfunction "VDD_CORE_P9") (pintype "power_in"))
      (node (ref "U1") (pin "R10") (pinfunction "VDD_CORE_R10") (pintype "power_in"))
      (node (ref "U3") (pin "E3") (pinfunction "FB_E3") (pintype "input"))
    )
    (net (code "23") (name "unconnected-(U2-ADJ{slash}NC-Pad2)") (class "Default")
      (node (ref "U2") (pin "2") (pinfunction "ADJ/NC_2") (pintype "output"))
    )
    (net (code "24") (name "unconnected-(U4-NC-Pad5)") (class "Default")
      (node (ref "U4") (pin "5") (pinfunction "NC_5") (pintype "passive"))
    )
    (net (code "25") (name "unconnected-(U4-NC-Pad11)") (class "Default")
      (node (ref "U4") (pin "11") (pinfunction "NC_11") (pintype "power_in"))
    )
  )
)
